# MAIN.net
KiCad netlist of a schematic drawn in Altium Designer
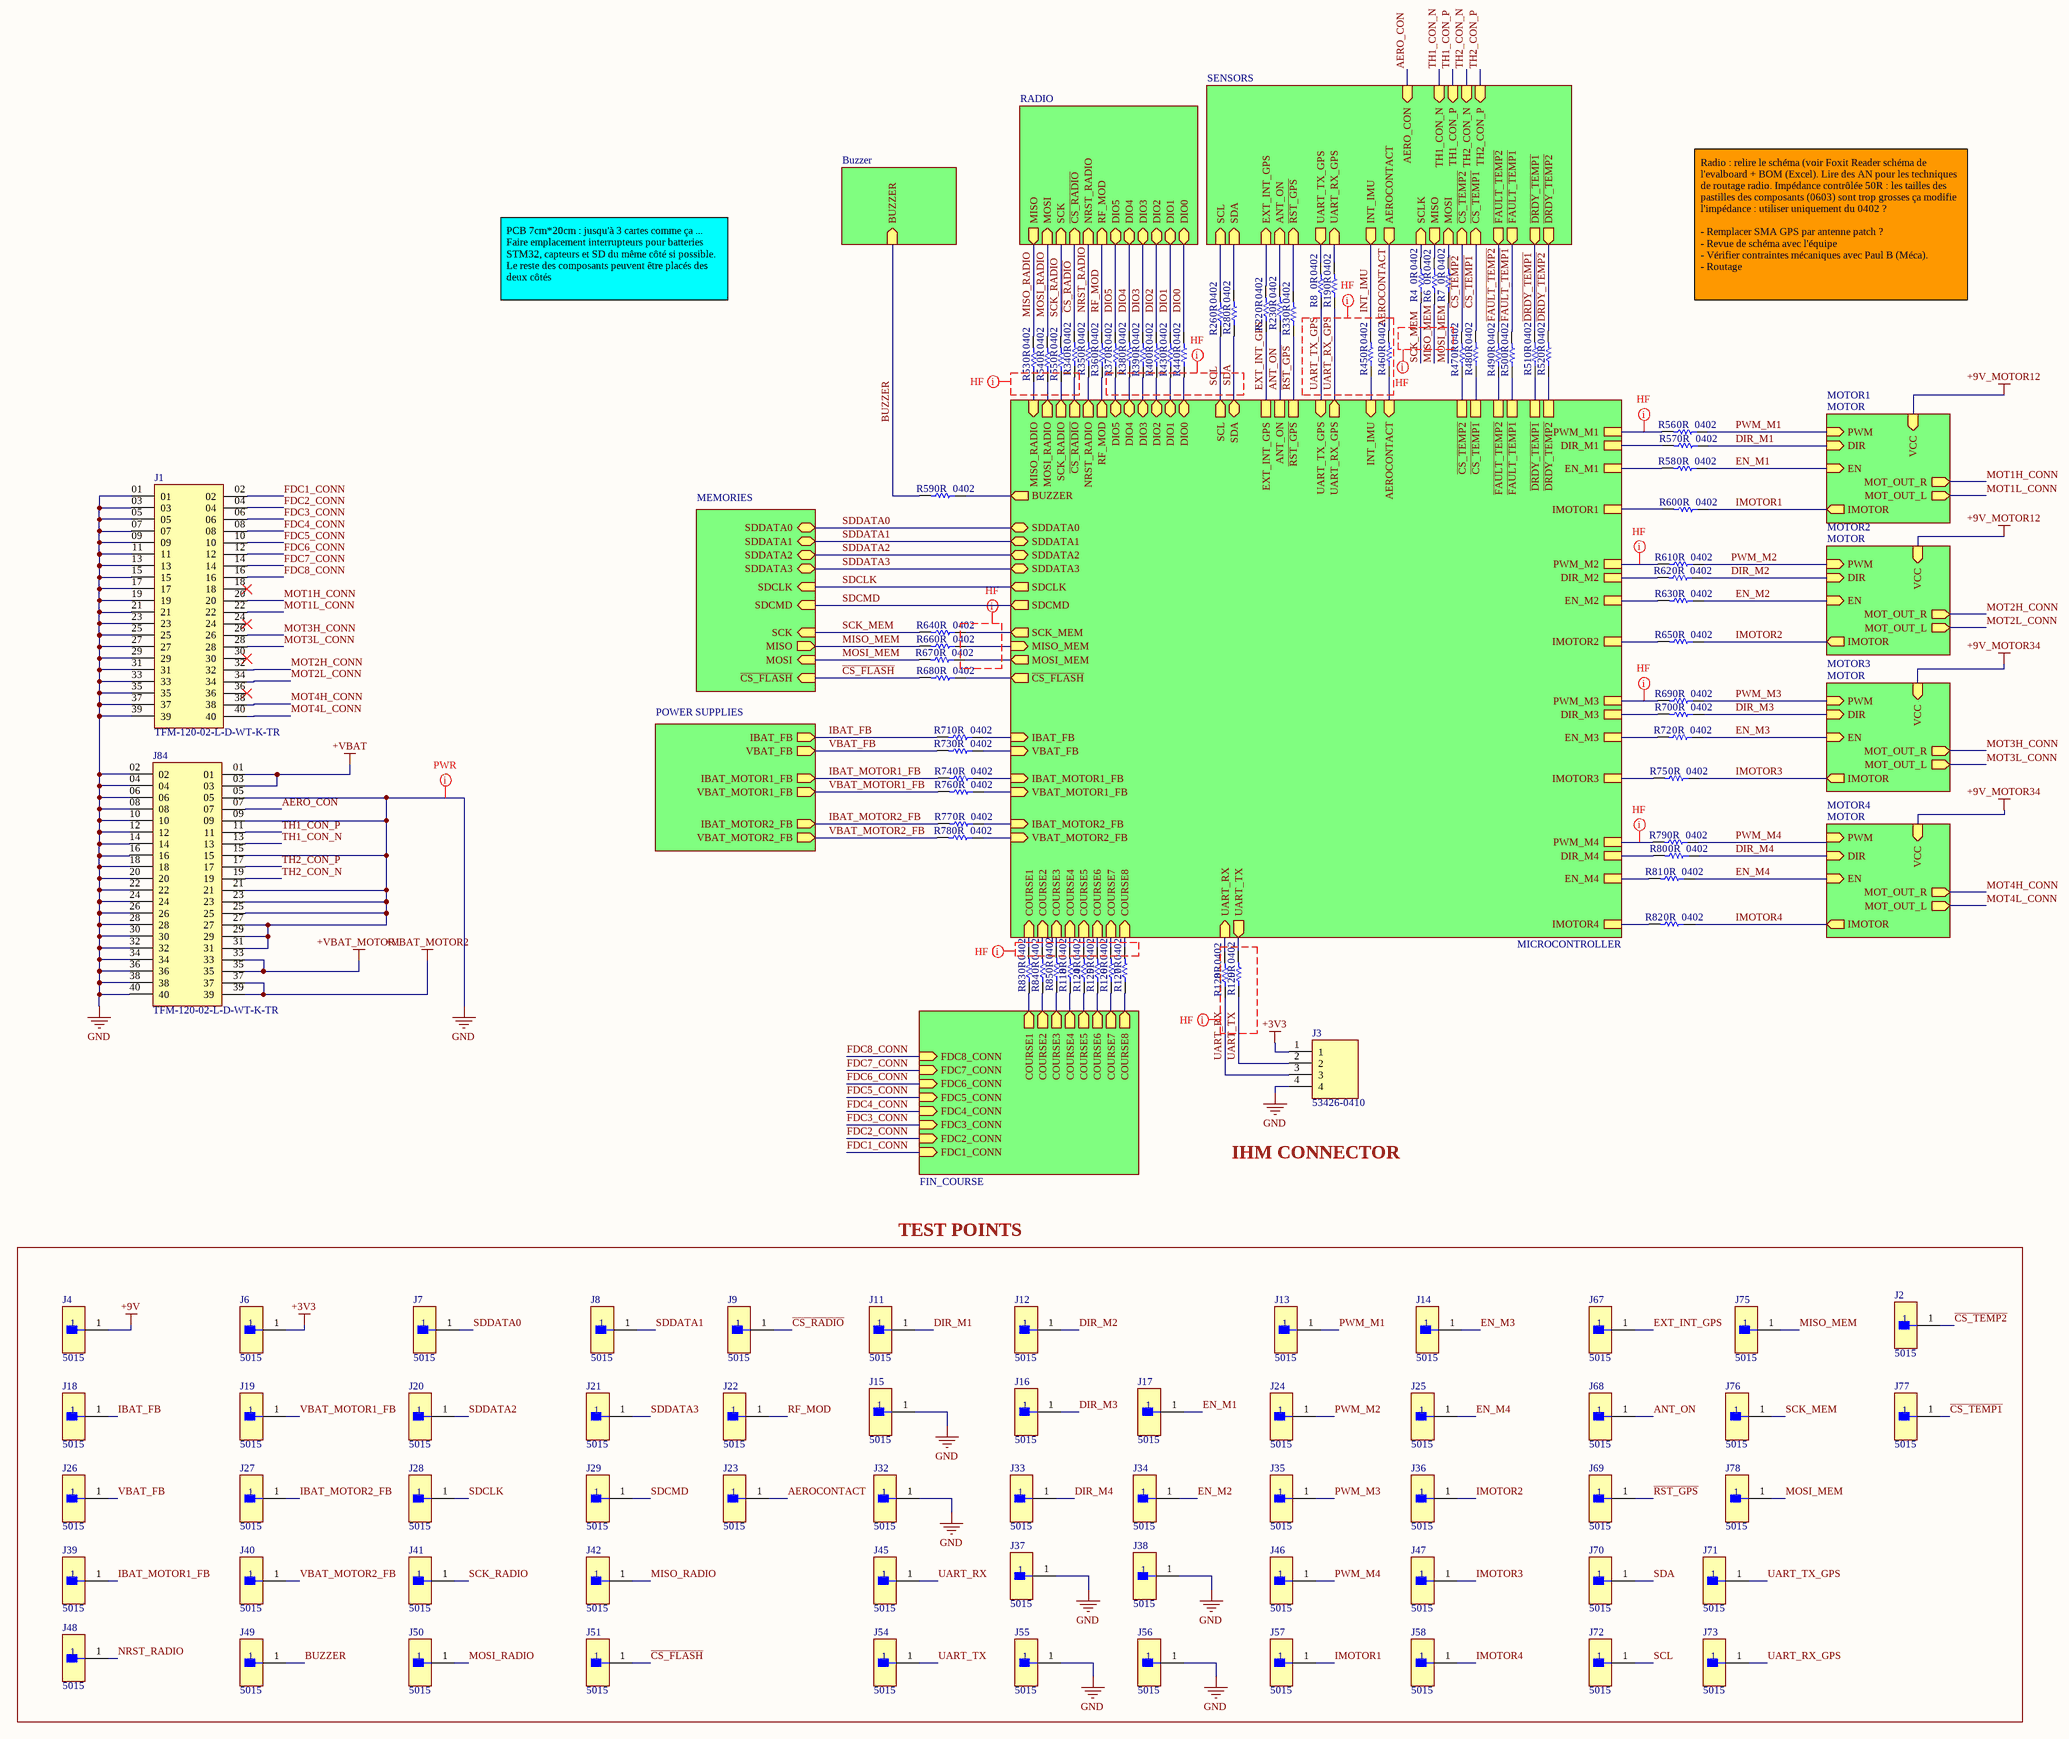
[diagram p0: MAIN.SchDoc]

(export (version "E")
  (design (tool "Eeschema 10.0.6"))
  (components
    (comp (ref "J1")
      (value "TFM-120-02-L-D-WT-K-TR")
      (footprint "TFM-120-02-L-D-WT:SAMTEC_TFM-120-02-L-D-WT-K-TR")
      (fields (field (name "MF") "{'manufacturer': u'Samtec'}"))
      (libsource (lib "*") (part "TFM-120-02-L-D-WT-K-TR"))
    )
    (comp (ref "J2")
      (value "5015")
      (footprint "FP-5015-MFG")
      (description "PC TEST POINT MINIATURE")
      (fields
        (field (name "MANUFACTURER") "keystone")
        (field (name "OCTOPART") "https://octopart.com/5015-keystone-3822")
      )
      (libsource (lib "Altium Content Vault") (part "dd45045ce8184df9e99e12baf3f412c"))
    )
    (comp (ref "J3")
      (value "53426-0410")
      (footprint "SamacSys:SHDRRA4W55P0X250_1X4_1240X1150X690P")
      (description "Connector")
      (fields (field (name "MOUSER PART NUMBER") "538-53426-0410"))
      (libsource (lib "*") (part "53426-0410"))
    )
    (comp (ref "J4")
      (value "5015")
      (footprint "FP-5015-MFG")
      (description "PC TEST POINT MINIATURE")
      (fields
        (field (name "MANUFACTURER") "keystone")
        (field (name "OCTOPART") "https://octopart.com/5015-keystone-3822")
      )
      (libsource (lib "Altium Content Vault") (part "dd45045ce8184df9e99e12baf3f412c"))
    )
    (comp (ref "J6")
      (value "5015")
      (footprint "FP-5015-MFG")
      (description "PC TEST POINT MINIATURE")
      (fields
        (field (name "MANUFACTURER") "keystone")
        (field (name "OCTOPART") "https://octopart.com/5015-keystone-3822")
      )
      (libsource (lib "Altium Content Vault") (part "dd45045ce8184df9e99e12baf3f412c"))
    )
    (comp (ref "J7")
      (value "5015")
      (footprint "FP-5015-MFG")
      (description "PC TEST POINT MINIATURE")
      (fields
        (field (name "MANUFACTURER") "keystone")
        (field (name "OCTOPART") "https://octopart.com/5015-keystone-3822")
      )
      (libsource (lib "Altium Content Vault") (part "dd45045ce8184df9e99e12baf3f412c"))
    )
    (comp (ref "J8")
      (value "5015")
      (footprint "FP-5015-MFG")
      (description "PC TEST POINT MINIATURE")
      (fields
        (field (name "MANUFACTURER") "keystone")
        (field (name "OCTOPART") "https://octopart.com/5015-keystone-3822")
      )
      (libsource (lib "Altium Content Vault") (part "dd45045ce8184df9e99e12baf3f412c"))
    )
    (comp (ref "J9")
      (value "5015")
      (footprint "FP-5015-MFG")
      (description "PC TEST POINT MINIATURE")
      (fields
        (field (name "MANUFACTURER") "keystone")
        (field (name "OCTOPART") "https://octopart.com/5015-keystone-3822")
      )
      (libsource (lib "Altium Content Vault") (part "dd45045ce8184df9e99e12baf3f412c"))
    )
    (comp (ref "J11")
      (value "5015")
      (footprint "FP-5015-MFG")
      (description "PC TEST POINT MINIATURE")
      (fields
        (field (name "MANUFACTURER") "keystone")
        (field (name "OCTOPART") "https://octopart.com/5015-keystone-3822")
      )
      (libsource (lib "Altium Content Vault") (part "dd45045ce8184df9e99e12baf3f412c"))
    )
    (comp (ref "J12")
      (value "5015")
      (footprint "FP-5015-MFG")
      (description "PC TEST POINT MINIATURE")
      (fields
        (field (name "MANUFACTURER") "keystone")
        (field (name "OCTOPART") "https://octopart.com/5015-keystone-3822")
      )
      (libsource (lib "Altium Content Vault") (part "dd45045ce8184df9e99e12baf3f412c"))
    )
    (comp (ref "J13")
      (value "5015")
      (footprint "FP-5015-MFG")
      (description "PC TEST POINT MINIATURE")
      (fields
        (field (name "MANUFACTURER") "keystone")
        (field (name "OCTOPART") "https://octopart.com/5015-keystone-3822")
      )
      (libsource (lib "Altium Content Vault") (part "dd45045ce8184df9e99e12baf3f412c"))
    )
    (comp (ref "J14")
      (value "5015")
      (footprint "FP-5015-MFG")
      (description "PC TEST POINT MINIATURE")
      (fields
        (field (name "MANUFACTURER") "keystone")
        (field (name "OCTOPART") "https://octopart.com/5015-keystone-3822")
      )
      (libsource (lib "Altium Content Vault") (part "dd45045ce8184df9e99e12baf3f412c"))
    )
    (comp (ref "J15")
      (value "5015")
      (footprint "FP-5015-MFG")
      (description "PC TEST POINT MINIATURE")
      (fields
        (field (name "MANUFACTURER") "keystone")
        (field (name "OCTOPART") "https://octopart.com/5015-keystone-3822")
      )
      (libsource (lib "Altium Content Vault") (part "dd45045ce8184df9e99e12baf3f412c"))
    )
    (comp (ref "J16")
      (value "5015")
      (footprint "FP-5015-MFG")
      (description "PC TEST POINT MINIATURE")
      (fields
        (field (name "MANUFACTURER") "keystone")
        (field (name "OCTOPART") "https://octopart.com/5015-keystone-3822")
      )
      (libsource (lib "Altium Content Vault") (part "dd45045ce8184df9e99e12baf3f412c"))
    )
    (comp (ref "J17")
      (value "5015")
      (footprint "FP-5015-MFG")
      (description "PC TEST POINT MINIATURE")
      (fields
        (field (name "MANUFACTURER") "keystone")
        (field (name "OCTOPART") "https://octopart.com/5015-keystone-3822")
      )
      (libsource (lib "Altium Content Vault") (part "dd45045ce8184df9e99e12baf3f412c"))
    )
    (comp (ref "J18")
      (value "5015")
      (footprint "FP-5015-MFG")
      (description "PC TEST POINT MINIATURE")
      (fields
        (field (name "MANUFACTURER") "keystone")
        (field (name "OCTOPART") "https://octopart.com/5015-keystone-3822")
      )
      (libsource (lib "Altium Content Vault") (part "dd45045ce8184df9e99e12baf3f412c"))
    )
    (comp (ref "J19")
      (value "5015")
      (footprint "FP-5015-MFG")
      (description "PC TEST POINT MINIATURE")
      (fields
        (field (name "MANUFACTURER") "keystone")
        (field (name "OCTOPART") "https://octopart.com/5015-keystone-3822")
      )
      (libsource (lib "Altium Content Vault") (part "dd45045ce8184df9e99e12baf3f412c"))
    )
    (comp (ref "J20")
      (value "5015")
      (footprint "FP-5015-MFG")
      (description "PC TEST POINT MINIATURE")
      (fields
        (field (name "MANUFACTURER") "keystone")
        (field (name "OCTOPART") "https://octopart.com/5015-keystone-3822")
      )
      (libsource (lib "Altium Content Vault") (part "dd45045ce8184df9e99e12baf3f412c"))
    )
    (comp (ref "J21")
      (value "5015")
      (footprint "FP-5015-MFG")
      (description "PC TEST POINT MINIATURE")
      (fields
        (field (name "MANUFACTURER") "keystone")
        (field (name "OCTOPART") "https://octopart.com/5015-keystone-3822")
      )
      (libsource (lib "Altium Content Vault") (part "dd45045ce8184df9e99e12baf3f412c"))
    )
    (comp (ref "J22")
      (value "5015")
      (footprint "FP-5015-MFG")
      (description "PC TEST POINT MINIATURE")
      (fields
        (field (name "MANUFACTURER") "keystone")
        (field (name "OCTOPART") "https://octopart.com/5015-keystone-3822")
      )
      (libsource (lib "Altium Content Vault") (part "dd45045ce8184df9e99e12baf3f412c"))
    )
    (comp (ref "J23")
      (value "5015")
      (footprint "FP-5015-MFG")
      (description "PC TEST POINT MINIATURE")
      (fields
        (field (name "MANUFACTURER") "keystone")
        (field (name "OCTOPART") "https://octopart.com/5015-keystone-3822")
      )
      (libsource (lib "Altium Content Vault") (part "dd45045ce8184df9e99e12baf3f412c"))
    )
    (comp (ref "J24")
      (value "5015")
      (footprint "FP-5015-MFG")
      (description "PC TEST POINT MINIATURE")
      (fields
        (field (name "MANUFACTURER") "keystone")
        (field (name "OCTOPART") "https://octopart.com/5015-keystone-3822")
      )
      (libsource (lib "Altium Content Vault") (part "dd45045ce8184df9e99e12baf3f412c"))
    )
    (comp (ref "J25")
      (value "5015")
      (footprint "FP-5015-MFG")
      (description "PC TEST POINT MINIATURE")
      (fields
        (field (name "MANUFACTURER") "keystone")
        (field (name "OCTOPART") "https://octopart.com/5015-keystone-3822")
      )
      (libsource (lib "Altium Content Vault") (part "dd45045ce8184df9e99e12baf3f412c"))
    )
    (comp (ref "J26")
      (value "5015")
      (footprint "FP-5015-MFG")
      (description "PC TEST POINT MINIATURE")
      (fields
        (field (name "MANUFACTURER") "keystone")
        (field (name "OCTOPART") "https://octopart.com/5015-keystone-3822")
      )
      (libsource (lib "Altium Content Vault") (part "dd45045ce8184df9e99e12baf3f412c"))
    )
    (comp (ref "J27")
      (value "5015")
      (footprint "FP-5015-MFG")
      (description "PC TEST POINT MINIATURE")
      (fields
        (field (name "MANUFACTURER") "keystone")
        (field (name "OCTOPART") "https://octopart.com/5015-keystone-3822")
      )
      (libsource (lib "Altium Content Vault") (part "dd45045ce8184df9e99e12baf3f412c"))
    )
    (comp (ref "J28")
      (value "5015")
      (footprint "FP-5015-MFG")
      (description "PC TEST POINT MINIATURE")
      (fields
        (field (name "MANUFACTURER") "keystone")
        (field (name "OCTOPART") "https://octopart.com/5015-keystone-3822")
      )
      (libsource (lib "Altium Content Vault") (part "dd45045ce8184df9e99e12baf3f412c"))
    )
    (comp (ref "J29")
      (value "5015")
      (footprint "FP-5015-MFG")
      (description "PC TEST POINT MINIATURE")
      (fields
        (field (name "MANUFACTURER") "keystone")
        (field (name "OCTOPART") "https://octopart.com/5015-keystone-3822")
      )
      (libsource (lib "Altium Content Vault") (part "dd45045ce8184df9e99e12baf3f412c"))
    )
    (comp (ref "J32")
      (value "5015")
      (footprint "FP-5015-MFG")
      (description "PC TEST POINT MINIATURE")
      (fields
        (field (name "MANUFACTURER") "keystone")
        (field (name "OCTOPART") "https://octopart.com/5015-keystone-3822")
      )
      (libsource (lib "Altium Content Vault") (part "dd45045ce8184df9e99e12baf3f412c"))
    )
    (comp (ref "J33")
      (value "5015")
      (footprint "FP-5015-MFG")
      (description "PC TEST POINT MINIATURE")
      (fields
        (field (name "MANUFACTURER") "keystone")
        (field (name "OCTOPART") "https://octopart.com/5015-keystone-3822")
      )
      (libsource (lib "Altium Content Vault") (part "dd45045ce8184df9e99e12baf3f412c"))
    )
    (comp (ref "J34")
      (value "5015")
      (footprint "FP-5015-MFG")
      (description "PC TEST POINT MINIATURE")
      (fields
        (field (name "MANUFACTURER") "keystone")
        (field (name "OCTOPART") "https://octopart.com/5015-keystone-3822")
      )
      (libsource (lib "Altium Content Vault") (part "dd45045ce8184df9e99e12baf3f412c"))
    )
    (comp (ref "J35")
      (value "5015")
      (footprint "FP-5015-MFG")
      (description "PC TEST POINT MINIATURE")
      (fields
        (field (name "MANUFACTURER") "keystone")
        (field (name "OCTOPART") "https://octopart.com/5015-keystone-3822")
      )
      (libsource (lib "Altium Content Vault") (part "dd45045ce8184df9e99e12baf3f412c"))
    )
    (comp (ref "J36")
      (value "5015")
      (footprint "FP-5015-MFG")
      (description "PC TEST POINT MINIATURE")
      (fields
        (field (name "MANUFACTURER") "keystone")
        (field (name "OCTOPART") "https://octopart.com/5015-keystone-3822")
      )
      (libsource (lib "Altium Content Vault") (part "dd45045ce8184df9e99e12baf3f412c"))
    )
    (comp (ref "J37")
      (value "5015")
      (footprint "FP-5015-MFG")
      (description "PC TEST POINT MINIATURE")
      (fields
        (field (name "MANUFACTURER") "keystone")
        (field (name "OCTOPART") "https://octopart.com/5015-keystone-3822")
      )
      (libsource (lib "Altium Content Vault") (part "dd45045ce8184df9e99e12baf3f412c"))
    )
    (comp (ref "J38")
      (value "5015")
      (footprint "FP-5015-MFG")
      (description "PC TEST POINT MINIATURE")
      (fields
        (field (name "MANUFACTURER") "keystone")
        (field (name "OCTOPART") "https://octopart.com/5015-keystone-3822")
      )
      (libsource (lib "Altium Content Vault") (part "dd45045ce8184df9e99e12baf3f412c"))
    )
    (comp (ref "J39")
      (value "5015")
      (footprint "FP-5015-MFG")
      (description "PC TEST POINT MINIATURE")
      (fields
        (field (name "MANUFACTURER") "keystone")
        (field (name "OCTOPART") "https://octopart.com/5015-keystone-3822")
      )
      (libsource (lib "Altium Content Vault") (part "dd45045ce8184df9e99e12baf3f412c"))
    )
    (comp (ref "J40")
      (value "5015")
      (footprint "FP-5015-MFG")
      (description "PC TEST POINT MINIATURE")
      (fields
        (field (name "MANUFACTURER") "keystone")
        (field (name "OCTOPART") "https://octopart.com/5015-keystone-3822")
      )
      (libsource (lib "Altium Content Vault") (part "dd45045ce8184df9e99e12baf3f412c"))
    )
    (comp (ref "J41")
      (value "5015")
      (footprint "FP-5015-MFG")
      (description "PC TEST POINT MINIATURE")
      (fields
        (field (name "MANUFACTURER") "keystone")
        (field (name "OCTOPART") "https://octopart.com/5015-keystone-3822")
      )
      (libsource (lib "Altium Content Vault") (part "dd45045ce8184df9e99e12baf3f412c"))
    )
    (comp (ref "J42")
      (value "5015")
      (footprint "FP-5015-MFG")
      (description "PC TEST POINT MINIATURE")
      (fields
        (field (name "MANUFACTURER") "keystone")
        (field (name "OCTOPART") "https://octopart.com/5015-keystone-3822")
      )
      (libsource (lib "Altium Content Vault") (part "dd45045ce8184df9e99e12baf3f412c"))
    )
    (comp (ref "J45")
      (value "5015")
      (footprint "FP-5015-MFG")
      (description "PC TEST POINT MINIATURE")
      (fields
        (field (name "MANUFACTURER") "keystone")
        (field (name "OCTOPART") "https://octopart.com/5015-keystone-3822")
      )
      (libsource (lib "Altium Content Vault") (part "dd45045ce8184df9e99e12baf3f412c"))
    )
    (comp (ref "J46")
      (value "5015")
      (footprint "FP-5015-MFG")
      (description "PC TEST POINT MINIATURE")
      (fields
        (field (name "MANUFACTURER") "keystone")
        (field (name "OCTOPART") "https://octopart.com/5015-keystone-3822")
      )
      (libsource (lib "Altium Content Vault") (part "dd45045ce8184df9e99e12baf3f412c"))
    )
    (comp (ref "J47")
      (value "5015")
      (footprint "FP-5015-MFG")
      (description "PC TEST POINT MINIATURE")
      (fields
        (field (name "MANUFACTURER") "keystone")
        (field (name "OCTOPART") "https://octopart.com/5015-keystone-3822")
      )
      (libsource (lib "Altium Content Vault") (part "dd45045ce8184df9e99e12baf3f412c"))
    )
    (comp (ref "J48")
      (value "5015")
      (footprint "FP-5015-MFG")
      (description "PC TEST POINT MINIATURE")
      (fields
        (field (name "MANUFACTURER") "keystone")
        (field (name "OCTOPART") "https://octopart.com/5015-keystone-3822")
      )
      (libsource (lib "Altium Content Vault") (part "dd45045ce8184df9e99e12baf3f412c"))
    )
    (comp (ref "J49")
      (value "5015")
      (footprint "FP-5015-MFG")
      (description "PC TEST POINT MINIATURE")
      (fields
        (field (name "MANUFACTURER") "keystone")
        (field (name "OCTOPART") "https://octopart.com/5015-keystone-3822")
      )
      (libsource (lib "Altium Content Vault") (part "dd45045ce8184df9e99e12baf3f412c"))
    )
    (comp (ref "J50")
      (value "5015")
      (footprint "FP-5015-MFG")
      (description "PC TEST POINT MINIATURE")
      (fields
        (field (name "MANUFACTURER") "keystone")
        (field (name "OCTOPART") "https://octopart.com/5015-keystone-3822")
      )
      (libsource (lib "Altium Content Vault") (part "dd45045ce8184df9e99e12baf3f412c"))
    )
    (comp (ref "J51")
      (value "5015")
      (footprint "FP-5015-MFG")
      (description "PC TEST POINT MINIATURE")
      (fields
        (field (name "MANUFACTURER") "keystone")
        (field (name "OCTOPART") "https://octopart.com/5015-keystone-3822")
      )
      (libsource (lib "Altium Content Vault") (part "dd45045ce8184df9e99e12baf3f412c"))
    )
    (comp (ref "J54")
      (value "5015")
      (footprint "FP-5015-MFG")
      (description "PC TEST POINT MINIATURE")
      (fields
        (field (name "MANUFACTURER") "keystone")
        (field (name "OCTOPART") "https://octopart.com/5015-keystone-3822")
      )
      (libsource (lib "Altium Content Vault") (part "dd45045ce8184df9e99e12baf3f412c"))
    )
    (comp (ref "J55")
      (value "5015")
      (footprint "FP-5015-MFG")
      (description "PC TEST POINT MINIATURE")
      (fields
        (field (name "MANUFACTURER") "keystone")
        (field (name "OCTOPART") "https://octopart.com/5015-keystone-3822")
      )
      (libsource (lib "Altium Content Vault") (part "dd45045ce8184df9e99e12baf3f412c"))
    )
    (comp (ref "J56")
      (value "5015")
      (footprint "FP-5015-MFG")
      (description "PC TEST POINT MINIATURE")
      (fields
        (field (name "MANUFACTURER") "keystone")
        (field (name "OCTOPART") "https://octopart.com/5015-keystone-3822")
      )
      (libsource (lib "Altium Content Vault") (part "dd45045ce8184df9e99e12baf3f412c"))
    )
    (comp (ref "J57")
      (value "5015")
      (footprint "FP-5015-MFG")
      (description "PC TEST POINT MINIATURE")
      (fields
        (field (name "MANUFACTURER") "keystone")
        (field (name "OCTOPART") "https://octopart.com/5015-keystone-3822")
      )
      (libsource (lib "Altium Content Vault") (part "dd45045ce8184df9e99e12baf3f412c"))
    )
    (comp (ref "J58")
      (value "5015")
      (footprint "FP-5015-MFG")
      (description "PC TEST POINT MINIATURE")
      (fields
        (field (name "MANUFACTURER") "keystone")
        (field (name "OCTOPART") "https://octopart.com/5015-keystone-3822")
      )
      (libsource (lib "Altium Content Vault") (part "dd45045ce8184df9e99e12baf3f412c"))
    )
    (comp (ref "J67")
      (value "5015")
      (footprint "FP-5015-MFG")
      (description "PC TEST POINT MINIATURE")
      (fields
        (field (name "MANUFACTURER") "keystone")
        (field (name "OCTOPART") "https://octopart.com/5015-keystone-3822")
      )
      (libsource (lib "Altium Content Vault") (part "dd45045ce8184df9e99e12baf3f412c"))
    )
    (comp (ref "J68")
      (value "5015")
      (footprint "FP-5015-MFG")
      (description "PC TEST POINT MINIATURE")
      (fields
        (field (name "MANUFACTURER") "keystone")
        (field (name "OCTOPART") "https://octopart.com/5015-keystone-3822")
      )
      (libsource (lib "Altium Content Vault") (part "dd45045ce8184df9e99e12baf3f412c"))
    )
    (comp (ref "J69")
      (value "5015")
      (footprint "FP-5015-MFG")
      (description "PC TEST POINT MINIATURE")
      (fields
        (field (name "MANUFACTURER") "keystone")
        (field (name "OCTOPART") "https://octopart.com/5015-keystone-3822")
      )
      (libsource (lib "Altium Content Vault") (part "dd45045ce8184df9e99e12baf3f412c"))
    )
    (comp (ref "J70")
      (value "5015")
      (footprint "FP-5015-MFG")
      (description "PC TEST POINT MINIATURE")
      (fields
        (field (name "MANUFACTURER") "keystone")
        (field (name "OCTOPART") "https://octopart.com/5015-keystone-3822")
      )
      (libsource (lib "Altium Content Vault") (part "dd45045ce8184df9e99e12baf3f412c"))
    )
    (comp (ref "J71")
      (value "5015")
      (footprint "FP-5015-MFG")
      (description "PC TEST POINT MINIATURE")
      (fields
        (field (name "MANUFACTURER") "keystone")
        (field (name "OCTOPART") "https://octopart.com/5015-keystone-3822")
      )
      (libsource (lib "Altium Content Vault") (part "dd45045ce8184df9e99e12baf3f412c"))
    )
    (comp (ref "J72")
      (value "5015")
      (footprint "FP-5015-MFG")
      (description "PC TEST POINT MINIATURE")
      (fields
        (field (name "MANUFACTURER") "keystone")
        (field (name "OCTOPART") "https://octopart.com/5015-keystone-3822")
      )
      (libsource (lib "Altium Content Vault") (part "dd45045ce8184df9e99e12baf3f412c"))
    )
    (comp (ref "J73")
      (value "5015")
      (footprint "FP-5015-MFG")
      (description "PC TEST POINT MINIATURE")
      (fields
        (field (name "MANUFACTURER") "keystone")
        (field (name "OCTOPART") "https://octopart.com/5015-keystone-3822")
      )
      (libsource (lib "Altium Content Vault") (part "dd45045ce8184df9e99e12baf3f412c"))
    )
    (comp (ref "J75")
      (value "5015")
      (footprint "FP-5015-MFG")
      (description "PC TEST POINT MINIATURE")
      (fields
        (field (name "MANUFACTURER") "keystone")
        (field (name "OCTOPART") "https://octopart.com/5015-keystone-3822")
      )
      (libsource (lib "Altium Content Vault") (part "dd45045ce8184df9e99e12baf3f412c"))
    )
    (comp (ref "J76")
      (value "5015")
      (footprint "FP-5015-MFG")
      (description "PC TEST POINT MINIATURE")
      (fields
        (field (name "MANUFACTURER") "keystone")
        (field (name "OCTOPART") "https://octopart.com/5015-keystone-3822")
      )
      (libsource (lib "Altium Content Vault") (part "dd45045ce8184df9e99e12baf3f412c"))
    )
    (comp (ref "J77")
      (value "5015")
      (footprint "FP-5015-MFG")
      (description "PC TEST POINT MINIATURE")
      (fields
        (field (name "MANUFACTURER") "keystone")
        (field (name "OCTOPART") "https://octopart.com/5015-keystone-3822")
      )
      (libsource (lib "Altium Content Vault") (part "dd45045ce8184df9e99e12baf3f412c"))
    )
    (comp (ref "J78")
      (value "5015")
      (footprint "FP-5015-MFG")
      (description "PC TEST POINT MINIATURE")
      (fields
        (field (name "MANUFACTURER") "keystone")
        (field (name "OCTOPART") "https://octopart.com/5015-keystone-3822")
      )
      (libsource (lib "Altium Content Vault") (part "dd45045ce8184df9e99e12baf3f412c"))
    )
    (comp (ref "J84")
      (value "TFM-120-02-L-D-WT-K-TR")
      (footprint "TFM-120-02-L-D-WT:SAMTEC_TFM-120-02-L-D-WT-K-TR")
      (fields (field (name "MF") "{'manufacturer': u'Samtec'}"))
      (libsource (lib "") (part "TFM-120-02-L-D-WT-K-TR_1"))
    )
    (comp (ref "R4")
      (value "CRCW04020000Z0EDHP")
      (footprint "RESC1005X40X25ML05T10")
      (fields
        (field (name "MANUFACTURER") "Vishay Dale")
        (field (name "CASE CODE (IMPERIAL)") "0402")
        (field (name "RESISTANCE") "0R")
      )
      (libsource (lib "Altium Content Vault") (part "RES"))
    )
    (comp (ref "R6")
      (value "CRCW04020000Z0EDHP")
      (footprint "RESC1005X40X25ML05T10")
      (fields
        (field (name "MANUFACTURER") "Vishay Dale")
        (field (name "CASE CODE (IMPERIAL)") "0402")
        (field (name "RESISTANCE") "0R")
      )
      (libsource (lib "Altium Content Vault") (part "RES"))
    )
    (comp (ref "R7")
      (value "CRCW04020000Z0EDHP")
      (footprint "RESC1005X40X25ML05T10")
      (fields
        (field (name "MANUFACTURER") "Vishay Dale")
        (field (name "CASE CODE (IMPERIAL)") "0402")
        (field (name "RESISTANCE") "0R")
      )
      (libsource (lib "Altium Content Vault") (part "RES"))
    )
    (comp (ref "R8")
      (value "CRCW04020000Z0EDHP")
      (footprint "RESC1005X40X25ML05T10")
      (fields
        (field (name "MANUFACTURER") "Vishay Dale")
        (field (name "CASE CODE (IMPERIAL)") "0402")
        (field (name "RESISTANCE") "0R")
      )
      (libsource (lib "Altium Content Vault") (part "RES"))
    )
    (comp (ref "R19")
      (value "CRCW04020000Z0EDHP")
      (footprint "RESC1005X40X25ML05T10")
      (fields
        (field (name "MANUFACTURER") "Vishay Dale")
        (field (name "CASE CODE (IMPERIAL)") "0402")
        (field (name "RESISTANCE") "0R")
      )
      (libsource (lib "Altium Content Vault") (part "RES"))
    )
    (comp (ref "R22")
      (value "CRCW04020000Z0EDHP")
      (footprint "RESC1005X40X25ML05T10")
      (fields
        (field (name "MANUFACTURER") "Vishay Dale")
        (field (name "CASE CODE (IMPERIAL)") "0402")
        (field (name "RESISTANCE") "0R")
      )
      (libsource (lib "Altium Content Vault") (part "RES"))
    )
    (comp (ref "R23")
      (value "CRCW04020000Z0EDHP")
      (footprint "RESC1005X40X25ML05T10")
      (fields
        (field (name "MANUFACTURER") "Vishay Dale")
        (field (name "CASE CODE (IMPERIAL)") "0402")
        (field (name "RESISTANCE") "0R")
      )
      (libsource (lib "Altium Content Vault") (part "RES"))
    )
    (comp (ref "R26")
      (value "CRCW04020000Z0EDHP")
      (footprint "RESC1005X40X25ML05T10")
      (fields
        (field (name "MANUFACTURER") "Vishay Dale")
        (field (name "CASE CODE (IMPERIAL)") "0402")
        (field (name "RESISTANCE") "0R")
      )
      (libsource (lib "Altium Content Vault") (part "RES"))
    )
    (comp (ref "R28")
      (value "CRCW04020000Z0EDHP")
      (footprint "RESC1005X40X25ML05T10")
      (fields
        (field (name "MANUFACTURER") "Vishay Dale")
        (field (name "CASE CODE (IMPERIAL)") "0402")
        (field (name "RESISTANCE") "0R")
      )
      (libsource (lib "Altium Content Vault") (part "RES"))
    )
    (comp (ref "R33")
      (value "CRCW04020000Z0EDHP")
      (footprint "RESC1005X40X25ML05T10")
      (fields
        (field (name "MANUFACTURER") "Vishay Dale")
        (field (name "CASE CODE (IMPERIAL)") "0402")
        (field (name "RESISTANCE") "0R")
      )
      (libsource (lib "Altium Content Vault") (part "RES"))
    )
    (comp (ref "R34")
      (value "CRCW04020000Z0EDHP")
      (footprint "RESC1005X40X25ML05T10")
      (fields
        (field (name "MANUFACTURER") "Vishay Dale")
        (field (name "CASE CODE (IMPERIAL)") "0402")
        (field (name "RESISTANCE") "0R")
      )
      (libsource (lib "Altium Content Vault") (part "RES"))
    )
    (comp (ref "R35")
      (value "CRCW04020000Z0EDHP")
      (footprint "RESC1005X40X25ML05T10")
      (fields
        (field (name "MANUFACTURER") "Vishay Dale")
        (field (name "CASE CODE (IMPERIAL)") "0402")
        (field (name "RESISTANCE") "0R")
      )
      (libsource (lib "Altium Content Vault") (part "RES"))
    )
    (comp (ref "R36")
      (value "CRCW04020000Z0EDHP")
      (footprint "RESC1005X40X25ML05T10")
      (fields
        (field (name "MANUFACTURER") "Vishay Dale")
        (field (name "CASE CODE (IMPERIAL)") "0402")
        (field (name "RESISTANCE") "0R")
      )
      (libsource (lib "Altium Content Vault") (part "RES"))
    )
    (comp (ref "R37")
      (value "CRCW04020000Z0EDHP")
      (footprint "RESC1005X40X25ML05T10")
      (fields
        (field (name "MANUFACTURER") "Vishay Dale")
        (field (name "CASE CODE (IMPERIAL)") "0402")
        (field (name "RESISTANCE") "0R")
      )
      (libsource (lib "Altium Content Vault") (part "RES"))
    )
    (comp (ref "R38")
      (value "CRCW04020000Z0EDHP")
      (footprint "RESC1005X40X25ML05T10")
      (fields
        (field (name "MANUFACTURER") "Vishay Dale")
        (field (name "CASE CODE (IMPERIAL)") "0402")
        (field (name "RESISTANCE") "0R")
      )
      (libsource (lib "Altium Content Vault") (part "RES"))
    )
    (comp (ref "R39")
      (value "CRCW04020000Z0EDHP")
      (footprint "RESC1005X40X25ML05T10")
      (fields
        (field (name "MANUFACTURER") "Vishay Dale")
        (field (name "CASE CODE (IMPERIAL)") "0402")
        (field (name "RESISTANCE") "0R")
      )
      (libsource (lib "Altium Content Vault") (part "RES"))
    )
    (comp (ref "R40")
      (value "CRCW04020000Z0EDHP")
      (footprint "RESC1005X40X25ML05T10")
      (fields
        (field (name "MANUFACTURER") "Vishay Dale")
        (field (name "CASE CODE (IMPERIAL)") "0402")
        (field (name "RESISTANCE") "0R")
      )
      (libsource (lib "Altium Content Vault") (part "RES"))
    )
    (comp (ref "R43")
      (value "CRCW04020000Z0EDHP")
      (footprint "RESC1005X40X25ML05T10")
      (fields
        (field (name "MANUFACTURER") "Vishay Dale")
        (field (name "CASE CODE (IMPERIAL)") "0402")
        (field (name "RESISTANCE") "0R")
      )
      (libsource (lib "Altium Content Vault") (part "RES"))
    )
    (comp (ref "R44")
      (value "CRCW04020000Z0EDHP")
      (footprint "RESC1005X40X25ML05T10")
      (fields
        (field (name "MANUFACTURER") "Vishay Dale")
        (field (name "CASE CODE (IMPERIAL)") "0402")
        (field (name "RESISTANCE") "0R")
      )
      (libsource (lib "Altium Content Vault") (part "RES"))
    )
    (comp (ref "R45")
      (value "CRCW04020000Z0EDHP")
      (footprint "RESC1005X40X25ML05T10")
      (fields
        (field (name "MANUFACTURER") "Vishay Dale")
        (field (name "CASE CODE (IMPERIAL)") "0402")
        (field (name "RESISTANCE") "0R")
      )
      (libsource (lib "Altium Content Vault") (part "RES"))
    )
    (comp (ref "R46")
      (value "CRCW04020000Z0EDHP")
      (footprint "RESC1005X40X25ML05T10")
      (fields
        (field (name "MANUFACTURER") "Vishay Dale")
        (field (name "CASE CODE (IMPERIAL)") "0402")
        (field (name "RESISTANCE") "0R")
      )
      (libsource (lib "Altium Content Vault") (part "RES"))
    )
    (comp (ref "R47")
      (value "CRCW04020000Z0EDHP")
      (footprint "RESC1005X40X25ML05T10")
      (fields
        (field (name "MANUFACTURER") "Vishay Dale")
        (field (name "CASE CODE (IMPERIAL)") "0402")
        (field (name "RESISTANCE") "0R")
      )
      (libsource (lib "Altium Content Vault") (part "RES"))
    )
    (comp (ref "R48")
      (value "CRCW04020000Z0EDHP")
      (footprint "RESC1005X40X25ML05T10")
      (fields
        (field (name "MANUFACTURER") "Vishay Dale")
        (field (name "CASE CODE (IMPERIAL)") "0402")
        (field (name "RESISTANCE") "0R")
      )
      (libsource (lib "Altium Content Vault") (part "RES"))
    )
    (comp (ref "R49")
      (value "CRCW04020000Z0EDHP")
      (footprint "RESC1005X40X25ML05T10")
      (fields
        (field (name "MANUFACTURER") "Vishay Dale")
        (field (name "CASE CODE (IMPERIAL)") "0402")
        (field (name "RESISTANCE") "0R")
      )
      (libsource (lib "Altium Content Vault") (part "RES"))
    )
    (comp (ref "R50")
      (value "CRCW04020000Z0EDHP")
      (footprint "RESC1005X40X25ML05T10")
      (fields
        (field (name "MANUFACTURER") "Vishay Dale")
        (field (name "CASE CODE (IMPERIAL)") "0402")
        (field (name "RESISTANCE") "0R")
      )
      (libsource (lib "Altium Content Vault") (part "RES"))
    )
    (comp (ref "R51")
      (value "CRCW04020000Z0EDHP")
      (footprint "RESC1005X40X25ML05T10")
      (fields
        (field (name "MANUFACTURER") "Vishay Dale")
        (field (name "CASE CODE (IMPERIAL)") "0402")
        (field (name "RESISTANCE") "0R")
      )
      (libsource (lib "Altium Content Vault") (part "RES"))
    )
    (comp (ref "R52")
      (value "CRCW04020000Z0EDHP")
      (footprint "RESC1005X40X25ML05T10")
      (fields
        (field (name "MANUFACTURER") "Vishay Dale")
        (field (name "CASE CODE (IMPERIAL)") "0402")
        (field (name "RESISTANCE") "0R")
      )
      (libsource (lib "Altium Content Vault") (part "RES"))
    )
    (comp (ref "R53")
      (value "CRCW04020000Z0EDHP")
      (footprint "RESC1005X40X25ML05T10")
      (fields
        (field (name "MANUFACTURER") "Vishay Dale")
        (field (name "CASE CODE (IMPERIAL)") "0402")
        (field (name "RESISTANCE") "0R")
      )
      (libsource (lib "Altium Content Vault") (part "RES"))
    )
    (comp (ref "R54")
      (value "CRCW04020000Z0EDHP")
      (footprint "RESC1005X40X25ML05T10")
      (fields
        (field (name "MANUFACTURER") "Vishay Dale")
        (field (name "CASE CODE (IMPERIAL)") "0402")
        (field (name "RESISTANCE") "0R")
      )
      (libsource (lib "Altium Content Vault") (part "RES"))
    )
    (comp (ref "R55")
      (value "CRCW04020000Z0EDHP")
      (footprint "RESC1005X40X25ML05T10")
      (fields
        (field (name "MANUFACTURER") "Vishay Dale")
        (field (name "CASE CODE (IMPERIAL)") "0402")
        (field (name "RESISTANCE") "0R")
      )
      (libsource (lib "Altium Content Vault") (part "RES"))
    )
    (comp (ref "R56")
      (value "CRCW04020000Z0EDHP")
      (footprint "RESC1005X40X25ML05T10")
      (fields
        (field (name "MANUFACTURER") "Vishay Dale")
        (field (name "CASE CODE (IMPERIAL)") "0402")
        (field (name "RESISTANCE") "0R")
      )
      (libsource (lib "Altium Content Vault") (part "RES"))
    )
    (comp (ref "R57")
      (value "CRCW04020000Z0EDHP")
      (footprint "RESC1005X40X25ML05T10")
      (fields
        (field (name "MANUFACTURER") "Vishay Dale")
        (field (name "CASE CODE (IMPERIAL)") "0402")
        (field (name "RESISTANCE") "0R")
      )
      (libsource (lib "Altium Content Vault") (part "RES"))
    )
    (comp (ref "R58")
      (value "CRCW04020000Z0EDHP")
      (footprint "RESC1005X40X25ML05T10")
      (fields
        (field (name "MANUFACTURER") "Vishay Dale")
        (field (name "CASE CODE (IMPERIAL)") "0402")
        (field (name "RESISTANCE") "0R")
      )
      (libsource (lib "Altium Content Vault") (part "RES"))
    )
    (comp (ref "R59")
      (value "CRCW04020000Z0EDHP")
      (footprint "RESC1005X40X25ML05T10")
      (fields
        (field (name "MANUFACTURER") "Vishay Dale")
        (field (name "CASE CODE (IMPERIAL)") "0402")
        (field (name "RESISTANCE") "0R")
      )
      (libsource (lib "Altium Content Vault") (part "RES"))
    )
    (comp (ref "R60")
      (value "CRCW04020000Z0EDHP")
      (footprint "RESC1005X40X25ML05T10")
      (fields
        (field (name "MANUFACTURER") "Vishay Dale")
        (field (name "CASE CODE (IMPERIAL)") "0402")
        (field (name "RESISTANCE") "0R")
      )
      (libsource (lib "Altium Content Vault") (part "RES"))
    )
    (comp (ref "R61")
      (value "CRCW04020000Z0EDHP")
      (footprint "RESC1005X40X25ML05T10")
      (fields
        (field (name "MANUFACTURER") "Vishay Dale")
        (field (name "CASE CODE (IMPERIAL)") "0402")
        (field (name "RESISTANCE") "0R")
      )
      (libsource (lib "Altium Content Vault") (part "RES"))
    )
    (comp (ref "R62")
      (value "CRCW04020000Z0EDHP")
      (footprint "RESC1005X40X25ML05T10")
      (fields
        (field (name "MANUFACTURER") "Vishay Dale")
        (field (name "CASE CODE (IMPERIAL)") "0402")
        (field (name "RESISTANCE") "0R")
      )
      (libsource (lib "Altium Content Vault") (part "RES"))
    )
    (comp (ref "R63")
      (value "CRCW04020000Z0EDHP")
      (footprint "RESC1005X40X25ML05T10")
      (fields
        (field (name "MANUFACTURER") "Vishay Dale")
        (field (name "CASE CODE (IMPERIAL)") "0402")
        (field (name "RESISTANCE") "0R")
      )
      (libsource (lib "Altium Content Vault") (part "RES"))
    )
    (comp (ref "R64")
      (value "CRCW04020000Z0EDHP")
      (footprint "RESC1005X40X25ML05T10")
      (fields
        (field (name "MANUFACTURER") "Vishay Dale")
        (field (name "CASE CODE (IMPERIAL)") "0402")
        (field (name "RESISTANCE") "0R")
      )
      (libsource (lib "Altium Content Vault") (part "RES"))
    )
    (comp (ref "R65")
      (value "CRCW04020000Z0EDHP")
      (footprint "RESC1005X40X25ML05T10")
      (fields
        (field (name "MANUFACTURER") "Vishay Dale")
        (field (name "CASE CODE (IMPERIAL)") "0402")
        (field (name "RESISTANCE") "0R")
      )
      (libsource (lib "Altium Content Vault") (part "RES"))
    )
    (comp (ref "R66")
      (value "CRCW04020000Z0EDHP")
      (footprint "RESC1005X40X25ML05T10")
      (fields
        (field (name "MANUFACTURER") "Vishay Dale")
        (field (name "CASE CODE (IMPERIAL)") "0402")
        (field (name "RESISTANCE") "0R")
      )
      (libsource (lib "Altium Content Vault") (part "RES"))
    )
    (comp (ref "R67")
      (value "CRCW04020000Z0EDHP")
      (footprint "RESC1005X40X25ML05T10")
      (fields
        (field (name "MANUFACTURER") "Vishay Dale")
        (field (name "CASE CODE (IMPERIAL)") "0402")
        (field (name "RESISTANCE") "0R")
      )
      (libsource (lib "Altium Content Vault") (part "RES"))
    )
    (comp (ref "R68")
      (value "CRCW04020000Z0EDHP")
      (footprint "RESC1005X40X25ML05T10")
      (fields
        (field (name "MANUFACTURER") "Vishay Dale")
        (field (name "CASE CODE (IMPERIAL)") "0402")
        (field (name "RESISTANCE") "0R")
      )
      (libsource (lib "Altium Content Vault") (part "RES"))
    )
    (comp (ref "R69")
      (value "CRCW04020000Z0EDHP")
      (footprint "RESC1005X40X25ML05T10")
      (fields
        (field (name "MANUFACTURER") "Vishay Dale")
        (field (name "CASE CODE (IMPERIAL)") "0402")
        (field (name "RESISTANCE") "0R")
      )
      (libsource (lib "Altium Content Vault") (part "RES"))
    )
    (comp (ref "R70")
      (value "CRCW04020000Z0EDHP")
      (footprint "RESC1005X40X25ML05T10")
      (fields
        (field (name "MANUFACTURER") "Vishay Dale")
        (field (name "CASE CODE (IMPERIAL)") "0402")
        (field (name "RESISTANCE") "0R")
      )
      (libsource (lib "Altium Content Vault") (part "RES"))
    )
    (comp (ref "R71")
      (value "CRCW04020000Z0EDHP")
      (footprint "RESC1005X40X25ML05T10")
      (fields
        (field (name "MANUFACTURER") "Vishay Dale")
        (field (name "CASE CODE (IMPERIAL)") "0402")
        (field (name "RESISTANCE") "0R")
      )
      (libsource (lib "Altium Content Vault") (part "RES"))
    )
    (comp (ref "R72")
      (value "CRCW04020000Z0EDHP")
      (footprint "RESC1005X40X25ML05T10")
      (fields
        (field (name "MANUFACTURER") "Vishay Dale")
        (field (name "CASE CODE (IMPERIAL)") "0402")
        (field (name "RESISTANCE") "0R")
      )
      (libsource (lib "Altium Content Vault") (part "RES"))
    )
    (comp (ref "R73")
      (value "CRCW04020000Z0EDHP")
      (footprint "RESC1005X40X25ML05T10")
      (fields
        (field (name "MANUFACTURER") "Vishay Dale")
        (field (name "CASE CODE (IMPERIAL)") "0402")
        (field (name "RESISTANCE") "0R")
      )
      (libsource (lib "Altium Content Vault") (part "RES"))
    )
    (comp (ref "R74")
      (value "CRCW04020000Z0EDHP")
      (footprint "RESC1005X40X25ML05T10")
      (fields
        (field (name "MANUFACTURER") "Vishay Dale")
        (field (name "CASE CODE (IMPERIAL)") "0402")
        (field (name "RESISTANCE") "0R")
      )
      (libsource (lib "Altium Content Vault") (part "RES"))
    )
    (comp (ref "R75")
      (value "CRCW04020000Z0EDHP")
      (footprint "RESC1005X40X25ML05T10")
      (fields
        (field (name "MANUFACTURER") "Vishay Dale")
        (field (name "CASE CODE (IMPERIAL)") "0402")
        (field (name "RESISTANCE") "0R")
      )
      (libsource (lib "Altium Content Vault") (part "RES"))
    )
    (comp (ref "R76")
      (value "CRCW04020000Z0EDHP")
      (footprint "RESC1005X40X25ML05T10")
      (fields
        (field (name "MANUFACTURER") "Vishay Dale")
        (field (name "CASE CODE (IMPERIAL)") "0402")
        (field (name "RESISTANCE") "0R")
      )
      (libsource (lib "Altium Content Vault") (part "RES"))
    )
    (comp (ref "R77")
      (value "CRCW04020000Z0EDHP")
      (footprint "RESC1005X40X25ML05T10")
      (fields
        (field (name "MANUFACTURER") "Vishay Dale")
        (field (name "CASE CODE (IMPERIAL)") "0402")
        (field (name "RESISTANCE") "0R")
      )
      (libsource (lib "Altium Content Vault") (part "RES"))
    )
    (comp (ref "R78")
      (value "CRCW04020000Z0EDHP")
      (footprint "RESC1005X40X25ML05T10")
      (fields
        (field (name "MANUFACTURER") "Vishay Dale")
        (field (name "CASE CODE (IMPERIAL)") "0402")
        (field (name "RESISTANCE") "0R")
      )
      (libsource (lib "Altium Content Vault") (part "RES"))
    )
    (comp (ref "R79")
      (value "CRCW04020000Z0EDHP")
      (footprint "RESC1005X40X25ML05T10")
      (fields
        (field (name "MANUFACTURER") "Vishay Dale")
        (field (name "CASE CODE (IMPERIAL)") "0402")
        (field (name "RESISTANCE") "0R")
      )
      (libsource (lib "Altium Content Vault") (part "RES"))
    )
    (comp (ref "R80")
      (value "CRCW04020000Z0EDHP")
      (footprint "RESC1005X40X25ML05T10")
      (fields
        (field (name "MANUFACTURER") "Vishay Dale")
        (field (name "CASE CODE (IMPERIAL)") "0402")
        (field (name "RESISTANCE") "0R")
      )
      (libsource (lib "Altium Content Vault") (part "RES"))
    )
    (comp (ref "R81")
      (value "CRCW04020000Z0EDHP")
      (footprint "RESC1005X40X25ML05T10")
      (fields
        (field (name "MANUFACTURER") "Vishay Dale")
        (field (name "CASE CODE (IMPERIAL)") "0402")
        (field (name "RESISTANCE") "0R")
      )
      (libsource (lib "Altium Content Vault") (part "RES"))
    )
    (comp (ref "R82")
      (value "CRCW04020000Z0EDHP")
      (footprint "RESC1005X40X25ML05T10")
      (fields
        (field (name "MANUFACTURER") "Vishay Dale")
        (field (name "CASE CODE (IMPERIAL)") "0402")
        (field (name "RESISTANCE") "0R")
      )
      (libsource (lib "Altium Content Vault") (part "RES"))
    )
    (comp (ref "R83")
      (value "CRCW04020000Z0EDHP")
      (footprint "RESC1005X40X25ML05T10")
      (fields
        (field (name "MANUFACTURER") "Vishay Dale")
        (field (name "CASE CODE (IMPERIAL)") "0402")
        (field (name "RESISTANCE") "0R")
      )
      (libsource (lib "Altium Content Vault") (part "RES"))
    )
    (comp (ref "R84")
      (value "CRCW04020000Z0EDHP")
      (footprint "RESC1005X40X25ML05T10")
      (fields
        (field (name "MANUFACTURER") "Vishay Dale")
        (field (name "CASE CODE (IMPERIAL)") "0402")
        (field (name "RESISTANCE") "0R")
      )
      (libsource (lib "Altium Content Vault") (part "RES"))
    )
    (comp (ref "R85")
      (value "CRCW04020000Z0EDHP")
      (footprint "RESC1005X40X25ML05T10")
      (fields
        (field (name "MANUFACTURER") "Vishay Dale")
        (field (name "CASE CODE (IMPERIAL)") "0402")
        (field (name "RESISTANCE") "0R")
      )
      (libsource (lib "Altium Content Vault") (part "RES"))
    )
    (comp (ref "R118")
      (value "CRCW04020000Z0EDHP")
      (footprint "RESC1005X40X25ML05T10")
      (fields
        (field (name "MANUFACTURER") "Vishay Dale")
        (field (name "CASE CODE (IMPERIAL)") "0402")
        (field (name "RESISTANCE") "0R")
      )
      (libsource (lib "Altium Content Vault") (part "RES"))
    )
    (comp (ref "R124")
      (value "CRCW04020000Z0EDHP")
      (footprint "RESC1005X40X25ML05T10")
      (fields
        (field (name "MANUFACTURER") "Vishay Dale")
        (field (name "CASE CODE (IMPERIAL)") "0402")
        (field (name "RESISTANCE") "0R")
      )
      (libsource (lib "Altium Content Vault") (part "RES"))
    )
    (comp (ref "R125")
      (value "CRCW04020000Z0EDHP")
      (footprint "RESC1005X40X25ML05T10")
      (fields
        (field (name "MANUFACTURER") "Vishay Dale")
        (field (name "CASE CODE (IMPERIAL)") "0402")
        (field (name "RESISTANCE") "0R")
      )
      (libsource (lib "Altium Content Vault") (part "RES"))
    )
    (comp (ref "R126")
      (value "CRCW04020000Z0EDHP")
      (footprint "RESC1005X40X25ML05T10")
      (fields
        (field (name "MANUFACTURER") "Vishay Dale")
        (field (name "CASE CODE (IMPERIAL)") "0402")
        (field (name "RESISTANCE") "0R")
      )
      (libsource (lib "Altium Content Vault") (part "RES"))
    )
    (comp (ref "R127")
      (value "CRCW04020000Z0EDHP")
      (footprint "RESC1005X40X25ML05T10")
      (fields
        (field (name "MANUFACTURER") "Vishay Dale")
        (field (name "CASE CODE (IMPERIAL)") "0402")
        (field (name "RESISTANCE") "0R")
      )
      (libsource (lib "Altium Content Vault") (part "RES"))
    )
    (comp (ref "R128")
      (value "CRCW04020000Z0EDHP")
      (footprint "RESC1005X40X25ML05T10")
      (fields
        (field (name "MANUFACTURER") "Vishay Dale")
        (field (name "CASE CODE (IMPERIAL)") "0402")
        (field (name "RESISTANCE") "0R")
      )
      (libsource (lib "Altium Content Vault") (part "RES"))
    )
    (comp (ref "R129")
      (value "CRCW04020000Z0EDHP")
      (footprint "RESC1005X40X25ML05T10")
      (fields
        (field (name "MANUFACTURER") "Vishay Dale")
        (field (name "CASE CODE (IMPERIAL)") "0402")
        (field (name "RESISTANCE") "0R")
      )
      (libsource (lib "Altium Content Vault") (part "RES"))
    )
  )
  (nets
    (net (code "1") (name "+3V3") (class "Default")
      (node (ref "J3") (pin "1") (pinfunction "1_1") (pintype "passive"))
      (node (ref "J6") (pin "1") (pinfunction "1_1") (pintype "passive"))
    )
    (net (code "2") (name "+9V") (class "Default")
      (node (ref "J4") (pin "1") (pinfunction "1_1") (pintype "passive"))
    )
    (net (code "5") (name "+VBAT") (class "Default")
      (node (ref "J84") (pin "01") (pinfunction "01_01") (pintype "passive"))
      (node (ref "J84") (pin "03") (pinfunction "03_03") (pintype "passive"))
    )
    (net (code "6") (name "+VBAT_MOTOR1") (class "Default")
      (node (ref "J84") (pin "33") (pinfunction "33_33") (pintype "passive"))
      (node (ref "J84") (pin "35") (pinfunction "35_35") (pintype "passive"))
    )
    (net (code "7") (name "+VBAT_MOTOR2") (class "Default")
      (node (ref "J84") (pin "37") (pinfunction "37_37") (pintype "passive"))
      (node (ref "J84") (pin "39") (pinfunction "39_39") (pintype "passive"))
    )
    (net (code "8") (name "/AEROCONTACT") (class "Default")
      (node (ref "J23") (pin "1") (pinfunction "1_1") (pintype "passive"))
      (node (ref "R46") (pin "2") (pinfunction "2_2") (pintype "passive"))
    )
    (net (code "9") (name "/AEROCONTACT_1") (class "Default")
      (node (ref "R46") (pin "1") (pinfunction "1_1") (pintype "passive"))
    )
    (net (code "10") (name "/AERO_CON") (class "Default")
      (node (ref "J84") (pin "07") (pinfunction "07_07") (pintype "passive"))
    )
    (net (code "11") (name "/ANT_ON") (class "Default")
      (node (ref "J68") (pin "1") (pinfunction "1_1") (pintype "passive"))
      (node (ref "R23") (pin "1") (pinfunction "1_1") (pintype "passive"))
    )
    (net (code "12") (name "/ANT_ON_1") (class "Default")
      (node (ref "R23") (pin "2") (pinfunction "2_2") (pintype "passive"))
    )
    (net (code "13") (name "/BUZZER") (class "Default")
      (node (ref "J49") (pin "1") (pinfunction "1_1") (pintype "passive"))
      (node (ref "R59") (pin "2") (pinfunction "2_2") (pintype "passive"))
    )
    (net (code "14") (name "/BUZZER_1") (class "Default")
      (node (ref "R59") (pin "1") (pinfunction "1_1") (pintype "passive"))
    )
    (net (code "15") (name "/COURSE1") (class "Default")
      (node (ref "R83") (pin "2") (pinfunction "2_2") (pintype "passive"))
    )
    (net (code "16") (name "/COURSE1_1") (class "Default")
      (node (ref "R83") (pin "1") (pinfunction "1_1") (pintype "passive"))
    )
    (net (code "17") (name "/COURSE2") (class "Default")
      (node (ref "R84") (pin "2") (pinfunction "2_2") (pintype "passive"))
    )
    (net (code "18") (name "/COURSE2_1") (class "Default")
      (node (ref "R84") (pin "1") (pinfunction "1_1") (pintype "passive"))
    )
    (net (code "19") (name "/COURSE3") (class "Default")
      (node (ref "R85") (pin "2") (pinfunction "2_2") (pintype "passive"))
    )
    (net (code "20") (name "/COURSE3_1") (class "Default")
      (node (ref "R85") (pin "1") (pinfunction "1_1") (pintype "passive"))
    )
    (net (code "21") (name "/COURSE4") (class "Default")
      (node (ref "R118") (pin "2") (pinfunction "2_2") (pintype "passive"))
    )
    (net (code "22") (name "/COURSE4_1") (class "Default")
      (node (ref "R118") (pin "1") (pinfunction "1_1") (pintype "passive"))
    )
    (net (code "23") (name "/COURSE5") (class "Default")
      (node (ref "R124") (pin "2") (pinfunction "2_2") (pintype "passive"))
    )
    (net (code "24") (name "/COURSE5_1") (class "Default")
      (node (ref "R124") (pin "1") (pinfunction "1_1") (pintype "passive"))
    )
    (net (code "25") (name "/COURSE6") (class "Default")
      (node (ref "R125") (pin "2") (pinfunction "2_2") (pintype "passive"))
    )
    (net (code "26") (name "/COURSE6_1") (class "Default")
      (node (ref "R125") (pin "1") (pinfunction "1_1") (pintype "passive"))
    )
    (net (code "27") (name "/COURSE7") (class "Default")
      (node (ref "R126") (pin "2") (pinfunction "2_2") (pintype "passive"))
    )
    (net (code "28") (name "/COURSE7_1") (class "Default")
      (node (ref "R126") (pin "1") (pinfunction "1_1") (pintype "passive"))
    )
    (net (code "29") (name "/COURSE8") (class "Default")
      (node (ref "R127") (pin "2") (pinfunction "2_2") (pintype "passive"))
    )
    (net (code "30") (name "/COURSE8_1") (class "Default")
      (node (ref "R127") (pin "1") (pinfunction "1_1") (pintype "passive"))
    )
    (net (code "31") (name "/CS_FLASH") (class "Default")
      (node (ref "J51") (pin "1") (pinfunction "1_1") (pintype "passive"))
      (node (ref "R68") (pin "2") (pinfunction "2_2") (pintype "passive"))
    )
    (net (code "32") (name "/CS_FLASH_1") (class "Default")
      (node (ref "R68") (pin "1") (pinfunction "1_1") (pintype "passive"))
    )
    (net (code "33") (name "/CS_RADIO") (class "Default")
      (node (ref "J9") (pin "1") (pinfunction "1_1") (pintype "passive"))
      (node (ref "R34") (pin "2") (pinfunction "2_2") (pintype "passive"))
    )
    (net (code "34") (name "/CS_RADIO_1") (class "Default")
      (node (ref "R34") (pin "1") (pinfunction "1_1") (pintype "passive"))
    )
    (net (code "35") (name "/CS_TEMP1") (class "Default")
      (node (ref "J77") (pin "1") (pinfunction "1_1") (pintype "passive"))
      (node (ref "R48") (pin "2") (pinfunction "2_2") (pintype "passive"))
    )
    (net (code "36") (name "/CS_TEMP1_1") (class "Default")
      (node (ref "R48") (pin "1") (pinfunction "1_1") (pintype "passive"))
    )
    (net (code "37") (name "/CS_TEMP2") (class "Default")
      (node (ref "J2") (pin "1") (pinfunction "1_1") (pintype "passive"))
      (node (ref "R47") (pin "2") (pinfunction "2_2") (pintype "passive"))
    )
    (net (code "38") (name "/CS_TEMP2_1") (class "Default")
      (node (ref "R47") (pin "1") (pinfunction "1_1") (pintype "passive"))
    )
    (net (code "39") (name "/DIO0") (class "Default")
      (node (ref "R44") (pin "2") (pinfunction "2_2") (pintype "passive"))
    )
    (net (code "40") (name "/DIO0_1") (class "Default")
      (node (ref "R44") (pin "1") (pinfunction "1_1") (pintype "passive"))
    )
    (net (code "41") (name "/DIO1") (class "Default")
      (node (ref "R43") (pin "2") (pinfunction "2_2") (pintype "passive"))
    )
    (net (code "42") (name "/DIO1_1") (class "Default")
      (node (ref "R43") (pin "1") (pinfunction "1_1") (pintype "passive"))
    )
    (net (code "43") (name "/DIO2") (class "Default")
      (node (ref "R40") (pin "2") (pinfunction "2_2") (pintype "passive"))
    )
    (net (code "44") (name "/DIO2_1") (class "Default")
      (node (ref "R40") (pin "1") (pinfunction "1_1") (pintype "passive"))
    )
    (net (code "45") (name "/DIO3") (class "Default")
      (node (ref "R39") (pin "2") (pinfunction "2_2") (pintype "passive"))
    )
    (net (code "46") (name "/DIO3_1") (class "Default")
      (node (ref "R39") (pin "1") (pinfunction "1_1") (pintype "passive"))
    )
    (net (code "47") (name "/DIO4") (class "Default")
      (node (ref "R38") (pin "2") (pinfunction "2_2") (pintype "passive"))
    )
    (net (code "48") (name "/DIO4_1") (class "Default")
      (node (ref "R38") (pin "1") (pinfunction "1_1") (pintype "passive"))
    )
    (net (code "49") (name "/DIO5") (class "Default")
      (node (ref "R37") (pin "2") (pinfunction "2_2") (pintype "passive"))
    )
    (net (code "50") (name "/DIO5_1") (class "Default")
      (node (ref "R37") (pin "1") (pinfunction "1_1") (pintype "passive"))
    )
    (net (code "51") (name "/DIR_M1") (class "Default")
      (node (ref "J11") (pin "1") (pinfunction "1_1") (pintype "passive"))
      (node (ref "R57") (pin "1") (pinfunction "1_1") (pintype "passive"))
    )
    (net (code "52") (name "/DIR_M1_1") (class "Default")
      (node (ref "R57") (pin "2") (pinfunction "2_2") (pintype "passive"))
    )
    (net (code "53") (name "/DIR_M2") (class "Default")
      (node (ref "J12") (pin "1") (pinfunction "1_1") (pintype "passive"))
      (node (ref "R62") (pin "1") (pinfunction "1_1") (pintype "passive"))
    )
    (net (code "54") (name "/DIR_M2_1") (class "Default")
      (node (ref "R62") (pin "2") (pinfunction "2_2") (pintype "passive"))
    )
    (net (code "55") (name "/DIR_M3") (class "Default")
      (node (ref "J16") (pin "1") (pinfunction "1_1") (pintype "passive"))
      (node (ref "R70") (pin "1") (pinfunction "1_1") (pintype "passive"))
    )
    (net (code "56") (name "/DIR_M3_1") (class "Default")
      (node (ref "R70") (pin "2") (pinfunction "2_2") (pintype "passive"))
    )
    (net (code "57") (name "/DIR_M4") (class "Default")
      (node (ref "J33") (pin "1") (pinfunction "1_1") (pintype "passive"))
      (node (ref "R80") (pin "1") (pinfunction "1_1") (pintype "passive"))
    )
    (net (code "58") (name "/DIR_M4_1") (class "Default")
      (node (ref "R80") (pin "2") (pinfunction "2_2") (pintype "passive"))
    )
    (net (code "59") (name "/DRDY_TEMP1") (class "Default")
      (node (ref "R51") (pin "2") (pinfunction "2_2") (pintype "passive"))
    )
    (net (code "60") (name "/DRDY_TEMP1_1") (class "Default")
      (node (ref "R51") (pin "1") (pinfunction "1_1") (pintype "passive"))
    )
    (net (code "61") (name "/DRDY_TEMP2") (class "Default")
      (node (ref "R52") (pin "2") (pinfunction "2_2") (pintype "passive"))
    )
    (net (code "62") (name "/DRDY_TEMP2_1") (class "Default")
      (node (ref "R52") (pin "1") (pinfunction "1_1") (pintype "passive"))
    )
    (net (code "63") (name "/EN_M1") (class "Default")
      (node (ref "J17") (pin "1") (pinfunction "1_1") (pintype "passive"))
      (node (ref "R58") (pin "1") (pinfunction "1_1") (pintype "passive"))
    )
    (net (code "64") (name "/EN_M1_1") (class "Default")
      (node (ref "R58") (pin "2") (pinfunction "2_2") (pintype "passive"))
    )
    (net (code "65") (name "/EN_M2") (class "Default")
      (node (ref "J34") (pin "1") (pinfunction "1_1") (pintype "passive"))
      (node (ref "R63") (pin "1") (pinfunction "1_1") (pintype "passive"))
    )
    (net (code "66") (name "/EN_M2_1") (class "Default")
      (node (ref "R63") (pin "2") (pinfunction "2_2") (pintype "passive"))
    )
    (net (code "67") (name "/EN_M3") (class "Default")
      (node (ref "J14") (pin "1") (pinfunction "1_1") (pintype "passive"))
      (node (ref "R72") (pin "1") (pinfunction "1_1") (pintype "passive"))
    )
    (net (code "68") (name "/EN_M3_1") (class "Default")
      (node (ref "R72") (pin "2") (pinfunction "2_2") (pintype "passive"))
    )
    (net (code "69") (name "/EN_M4") (class "Default")
      (node (ref "J25") (pin "1") (pinfunction "1_1") (pintype "passive"))
      (node (ref "R81") (pin "1") (pinfunction "1_1") (pintype "passive"))
    )
    (net (code "70") (name "/EN_M4_1") (class "Default")
      (node (ref "R81") (pin "2") (pinfunction "2_2") (pintype "passive"))
    )
    (net (code "71") (name "/EXT_INT_GPS") (class "Default")
      (node (ref "J67") (pin "1") (pinfunction "1_1") (pintype "passive"))
      (node (ref "R22") (pin "1") (pinfunction "1_1") (pintype "passive"))
    )
    (net (code "72") (name "/EXT_INT_GPS_1") (class "Default")
      (node (ref "R22") (pin "2") (pinfunction "2_2") (pintype "passive"))
    )
    (net (code "73") (name "/FAULT_TEMP1") (class "Default")
      (node (ref "R50") (pin "2") (pinfunction "2_2") (pintype "passive"))
    )
    (net (code "74") (name "/FAULT_TEMP1_1") (class "Default")
      (node (ref "R50") (pin "1") (pinfunction "1_1") (pintype "passive"))
    )
    (net (code "75") (name "/FAULT_TEMP2") (class "Default")
      (node (ref "R49") (pin "2") (pinfunction "2_2") (pintype "passive"))
    )
    (net (code "76") (name "/FAULT_TEMP2_1") (class "Default")
      (node (ref "R49") (pin "1") (pinfunction "1_1") (pintype "passive"))
    )
    (net (code "77") (name "/FDC1_CONN") (class "Default")
      (node (ref "J1") (pin "02") (pinfunction "02_02") (pintype "passive"))
    )
    (net (code "78") (name "/FDC2_CONN") (class "Default")
      (node (ref "J1") (pin "04") (pinfunction "04_04") (pintype "passive"))
    )
    (net (code "79") (name "/FDC3_CONN") (class "Default")
      (node (ref "J1") (pin "06") (pinfunction "06_06") (pintype "passive"))
    )
    (net (code "80") (name "/FDC4_CONN") (class "Default")
      (node (ref "J1") (pin "08") (pinfunction "08_08") (pintype "passive"))
    )
    (net (code "81") (name "/FDC5_CONN") (class "Default")
      (node (ref "J1") (pin "10") (pinfunction "10_10") (pintype "passive"))
    )
    (net (code "82") (name "/FDC6_CONN") (class "Default")
      (node (ref "J1") (pin "12") (pinfunction "12_12") (pintype "passive"))
    )
    (net (code "83") (name "/FDC7_CONN") (class "Default")
      (node (ref "J1") (pin "14") (pinfunction "14_14") (pintype "passive"))
    )
    (net (code "84") (name "/FDC8_CONN") (class "Default")
      (node (ref "J1") (pin "16") (pinfunction "16_16") (pintype "passive"))
    )
    (net (code "85") (name "/IBAT_FB") (class "Default")
      (node (ref "J18") (pin "1") (pinfunction "1_1") (pintype "passive"))
      (node (ref "R71") (pin "2") (pinfunction "2_2") (pintype "passive"))
    )
    (net (code "86") (name "/IBAT_FB_1") (class "Default")
      (node (ref "R71") (pin "1") (pinfunction "1_1") (pintype "passive"))
    )
    (net (code "87") (name "/IBAT_MOTOR1_FB") (class "Default")
      (node (ref "J39") (pin "1") (pinfunction "1_1") (pintype "passive"))
      (node (ref "R74") (pin "2") (pinfunction "2_2") (pintype "passive"))
    )
    (net (code "88") (name "/IBAT_MOTOR1_FB_1") (class "Default")
      (node (ref "R74") (pin "1") (pinfunction "1_1") (pintype "passive"))
    )
    (net (code "89") (name "/IBAT_MOTOR2_FB") (class "Default")
      (node (ref "J27") (pin "1") (pinfunction "1_1") (pintype "passive"))
      (node (ref "R77") (pin "2") (pinfunction "2_2") (pintype "passive"))
    )
    (net (code "90") (name "/IBAT_MOTOR2_FB_1") (class "Default")
      (node (ref "R77") (pin "1") (pinfunction "1_1") (pintype "passive"))
    )
    (net (code "91") (name "/IMOTOR1") (class "Default")
      (node (ref "J57") (pin "1") (pinfunction "1_1") (pintype "passive"))
      (node (ref "R60") (pin "1") (pinfunction "1_1") (pintype "passive"))
    )
    (net (code "92") (name "/IMOTOR1_1") (class "Default")
      (node (ref "R60") (pin "2") (pinfunction "2_2") (pintype "passive"))
    )
    (net (code "93") (name "/IMOTOR2") (class "Default")
      (node (ref "J36") (pin "1") (pinfunction "1_1") (pintype "passive"))
      (node (ref "R65") (pin "1") (pinfunction "1_1") (pintype "passive"))
    )
    (net (code "94") (name "/IMOTOR2_1") (class "Default")
      (node (ref "R65") (pin "2") (pinfunction "2_2") (pintype "passive"))
    )
    (net (code "95") (name "/IMOTOR3") (class "Default")
      (node (ref "J47") (pin "1") (pinfunction "1_1") (pintype "passive"))
      (node (ref "R75") (pin "1") (pinfunction "1_1") (pintype "passive"))
    )
    (net (code "96") (name "/IMOTOR3_1") (class "Default")
      (node (ref "R75") (pin "2") (pinfunction "2_2") (pintype "passive"))
    )
    (net (code "97") (name "/IMOTOR4") (class "Default")
      (node (ref "J58") (pin "1") (pinfunction "1_1") (pintype "passive"))
      (node (ref "R82") (pin "1") (pinfunction "1_1") (pintype "passive"))
    )
    (net (code "98") (name "/IMOTOR4_1") (class "Default")
      (node (ref "R82") (pin "2") (pinfunction "2_2") (pintype "passive"))
    )
    (net (code "99") (name "/INT_IMU") (class "Default")
      (node (ref "R45") (pin "2") (pinfunction "2_2") (pintype "passive"))
    )
    (net (code "100") (name "/INT_IMU_1") (class "Default")
      (node (ref "R45") (pin "1") (pinfunction "1_1") (pintype "passive"))
    )
    (net (code "101") (name "/MISO") (class "Default")
      (node (ref "R6") (pin "2") (pinfunction "2_2") (pintype "passive"))
    )
    (net (code "102") (name "/MISO_MEM") (class "Default")
      (node (ref "J75") (pin "1") (pinfunction "1_1") (pintype "passive"))
      (node (ref "R6") (pin "1") (pinfunction "1_1") (pintype "passive"))
      (node (ref "R66") (pin "2") (pinfunction "2_2") (pintype "passive"))
    )
    (net (code "103") (name "/MISO_MEM_1") (class "Default")
      (node (ref "R66") (pin "1") (pinfunction "1_1") (pintype "passive"))
    )
    (net (code "104") (name "/MISO_RADIO") (class "Default")
      (node (ref "J42") (pin "1") (pinfunction "1_1") (pintype "passive"))
      (node (ref "R53") (pin "2") (pinfunction "2_2") (pintype "passive"))
    )
    (net (code "105") (name "/MISO_RADIO_1") (class "Default")
      (node (ref "R53") (pin "1") (pinfunction "1_1") (pintype "passive"))
    )
    (net (code "106") (name "/MOSI") (class "Default")
      (node (ref "R7") (pin "2") (pinfunction "2_2") (pintype "passive"))
    )
    (net (code "107") (name "/MOSI_MEM") (class "Default")
      (node (ref "J78") (pin "1") (pinfunction "1_1") (pintype "passive"))
      (node (ref "R67") (pin "2") (pinfunction "2_2") (pintype "passive"))
      (node (ref "R7") (pin "1") (pinfunction "1_1") (pintype "passive"))
    )
    (net (code "108") (name "/MOSI_MEM_1") (class "Default")
      (node (ref "R67") (pin "1") (pinfunction "1_1") (pintype "passive"))
    )
    (net (code "109") (name "/MOSI_RADIO") (class "Default")
      (node (ref "J50") (pin "1") (pinfunction "1_1") (pintype "passive"))
      (node (ref "R54") (pin "2") (pinfunction "2_2") (pintype "passive"))
    )
    (net (code "110") (name "/MOSI_RADIO_1") (class "Default")
      (node (ref "R54") (pin "1") (pinfunction "1_1") (pintype "passive"))
    )
    (net (code "111") (name "/MOT1H_CONN") (class "Default")
      (node (ref "J1") (pin "20") (pinfunction "20_20") (pintype "passive"))
    )
    (net (code "112") (name "/MOT1L_CONN") (class "Default")
      (node (ref "J1") (pin "22") (pinfunction "22_22") (pintype "passive"))
    )
    (net (code "113") (name "/MOT2H_CONN") (class "Default")
      (node (ref "J1") (pin "32") (pinfunction "32_32") (pintype "passive"))
    )
    (net (code "114") (name "/MOT2L_CONN") (class "Default")
      (node (ref "J1") (pin "34") (pinfunction "34_34") (pintype "passive"))
    )
    (net (code "115") (name "/MOT3H_CONN") (class "Default")
      (node (ref "J1") (pin "26") (pinfunction "26_26") (pintype "passive"))
    )
    (net (code "116") (name "/MOT3L_CONN") (class "Default")
      (node (ref "J1") (pin "28") (pinfunction "28_28") (pintype "passive"))
    )
    (net (code "117") (name "/MOT4H_CONN") (class "Default")
      (node (ref "J1") (pin "38") (pinfunction "38_38") (pintype "passive"))
    )
    (net (code "118") (name "/MOT4L_CONN") (class "Default")
      (node (ref "J1") (pin "40") (pinfunction "40_40") (pintype "passive"))
    )
    (net (code "119") (name "/NRST_RADIO") (class "Default")
      (node (ref "J48") (pin "1") (pinfunction "1_1") (pintype "passive"))
      (node (ref "R35") (pin "2") (pinfunction "2_2") (pintype "passive"))
    )
    (net (code "120") (name "/NRST_RADIO_1") (class "Default")
      (node (ref "R35") (pin "1") (pinfunction "1_1") (pintype "passive"))
    )
    (net (code "122") (name "/PWM_M1") (class "Default")
      (node (ref "J13") (pin "1") (pinfunction "1_1") (pintype "passive"))
      (node (ref "R56") (pin "1") (pinfunction "1_1") (pintype "passive"))
    )
    (net (code "123") (name "/PWM_M1_1") (class "Default")
      (node (ref "R56") (pin "2") (pinfunction "2_2") (pintype "passive"))
    )
    (net (code "124") (name "/PWM_M2") (class "Default")
      (node (ref "J24") (pin "1") (pinfunction "1_1") (pintype "passive"))
      (node (ref "R61") (pin "1") (pinfunction "1_1") (pintype "passive"))
    )
    (net (code "125") (name "/PWM_M2_1") (class "Default")
      (node (ref "R61") (pin "2") (pinfunction "2_2") (pintype "passive"))
    )
    (net (code "126") (name "/PWM_M3") (class "Default")
      (node (ref "J35") (pin "1") (pinfunction "1_1") (pintype "passive"))
      (node (ref "R69") (pin "1") (pinfunction "1_1") (pintype "passive"))
    )
    (net (code "127") (name "/PWM_M3_1") (class "Default")
      (node (ref "R69") (pin "2") (pinfunction "2_2") (pintype "passive"))
    )
    (net (code "128") (name "/PWM_M4") (class "Default")
      (node (ref "J46") (pin "1") (pinfunction "1_1") (pintype "passive"))
      (node (ref "R79") (pin "1") (pinfunction "1_1") (pintype "passive"))
    )
    (net (code "129") (name "/PWM_M4_1") (class "Default")
      (node (ref "R79") (pin "2") (pinfunction "2_2") (pintype "passive"))
    )
    (net (code "130") (name "/RF_MOD") (class "Default")
      (node (ref "J22") (pin "1") (pinfunction "1_1") (pintype "passive"))
      (node (ref "R36") (pin "2") (pinfunction "2_2") (pintype "passive"))
    )
    (net (code "131") (name "/RF_MOD_1") (class "Default")
      (node (ref "R36") (pin "1") (pinfunction "1_1") (pintype "passive"))
    )
    (net (code "132") (name "/RST_GPS") (class "Default")
      (node (ref "J69") (pin "1") (pinfunction "1_1") (pintype "passive"))
      (node (ref "R33") (pin "1") (pinfunction "1_1") (pintype "passive"))
    )
    (net (code "133") (name "/RST_GPS_1") (class "Default")
      (node (ref "R33") (pin "2") (pinfunction "2_2") (pintype "passive"))
    )
    (net (code "134") (name "/SCK_MEM") (class "Default")
      (node (ref "J76") (pin "1") (pinfunction "1_1") (pintype "passive"))
      (node (ref "R4") (pin "1") (pinfunction "1_1") (pintype "passive"))
      (node (ref "R64") (pin "2") (pinfunction "2_2") (pintype "passive"))
    )
    (net (code "135") (name "/SCK_MEM_1") (class "Default")
      (node (ref "R64") (pin "1") (pinfunction "1_1") (pintype "passive"))
    )
    (net (code "136") (name "/SCK_RADIO") (class "Default")
      (node (ref "J41") (pin "1") (pinfunction "1_1") (pintype "passive"))
      (node (ref "R55") (pin "2") (pinfunction "2_2") (pintype "passive"))
    )
    (net (code "137") (name "/SCK_RADIO_1") (class "Default")
      (node (ref "R55") (pin "1") (pinfunction "1_1") (pintype "passive"))
    )
    (net (code "138") (name "/SCL") (class "Default")
      (node (ref "J72") (pin "1") (pinfunction "1_1") (pintype "passive"))
      (node (ref "R26") (pin "1") (pinfunction "1_1") (pintype "passive"))
    )
    (net (code "139") (name "/SCLK") (class "Default")
      (node (ref "R4") (pin "2") (pinfunction "2_2") (pintype "passive"))
    )
    (net (code "140") (name "/SCL_1") (class "Default")
      (node (ref "R26") (pin "2") (pinfunction "2_2") (pintype "passive"))
    )
    (net (code "141") (name "/SDA") (class "Default")
      (node (ref "J70") (pin "1") (pinfunction "1_1") (pintype "passive"))
      (node (ref "R28") (pin "1") (pinfunction "1_1") (pintype "passive"))
    )
    (net (code "142") (name "/SDA_1") (class "Default")
      (node (ref "R28") (pin "2") (pinfunction "2_2") (pintype "passive"))
    )
    (net (code "143") (name "/SDCLK") (class "Default")
      (node (ref "J28") (pin "1") (pinfunction "1_1") (pintype "passive"))
    )
    (net (code "144") (name "/SDCMD") (class "Default")
      (node (ref "J29") (pin "1") (pinfunction "1_1") (pintype "passive"))
    )
    (net (code "145") (name "/SDDATA0") (class "Default")
      (node (ref "J7") (pin "1") (pinfunction "1_1") (pintype "passive"))
    )
    (net (code "146") (name "/SDDATA1") (class "Default")
      (node (ref "J8") (pin "1") (pinfunction "1_1") (pintype "passive"))
    )
    (net (code "147") (name "/SDDATA2") (class "Default")
      (node (ref "J20") (pin "1") (pinfunction "1_1") (pintype "passive"))
    )
    (net (code "148") (name "/SDDATA3") (class "Default")
      (node (ref "J21") (pin "1") (pinfunction "1_1") (pintype "passive"))
    )
    (net (code "149") (name "/TH1_CON_N") (class "Default")
      (node (ref "J84") (pin "13") (pinfunction "13_13") (pintype "passive"))
    )
    (net (code "150") (name "/TH1_CON_P") (class "Default")
      (node (ref "J84") (pin "11") (pinfunction "11_11") (pintype "passive"))
    )
    (net (code "151") (name "/TH2_CON_N") (class "Default")
      (node (ref "J84") (pin "19") (pinfunction "19_19") (pintype "passive"))
    )
    (net (code "152") (name "/TH2_CON_P") (class "Default")
      (node (ref "J84") (pin "17") (pinfunction "17_17") (pintype "passive"))
    )
    (net (code "153") (name "/UART_RX") (class "Default")
      (node (ref "J3") (pin "3") (pinfunction "3_3") (pintype "passive"))
      (node (ref "J45") (pin "1") (pinfunction "1_1") (pintype "passive"))
      (node (ref "R128") (pin "1") (pinfunction "1_1") (pintype "passive"))
    )
    (net (code "154") (name "/UART_RX_1") (class "Default")
      (node (ref "R128") (pin "2") (pinfunction "2_2") (pintype "passive"))
    )
    (net (code "155") (name "/UART_RX_GPS") (class "Default")
      (node (ref "J73") (pin "1") (pinfunction "1_1") (pintype "passive"))
      (node (ref "R19") (pin "1") (pinfunction "1_1") (pintype "passive"))
    )
    (net (code "156") (name "/UART_RX_GPS_1") (class "Default")
      (node (ref "R19") (pin "2") (pinfunction "2_2") (pintype "passive"))
    )
    (net (code "157") (name "/UART_TX") (class "Default")
      (node (ref "J3") (pin "2") (pinfunction "2_2") (pintype "passive"))
      (node (ref "J54") (pin "1") (pinfunction "1_1") (pintype "passive"))
      (node (ref "R129") (pin "1") (pinfunction "1_1") (pintype "passive"))
    )
    (net (code "158") (name "/UART_TX_1") (class "Default")
      (node (ref "R129") (pin "2") (pinfunction "2_2") (pintype "passive"))
    )
    (net (code "159") (name "/UART_TX_GPS") (class "Default")
      (node (ref "J71") (pin "1") (pinfunction "1_1") (pintype "passive"))
      (node (ref "R8") (pin "1") (pinfunction "1_1") (pintype "passive"))
    )
    (net (code "160") (name "/UART_TX_GPS_1") (class "Default")
      (node (ref "R8") (pin "2") (pinfunction "2_2") (pintype "passive"))
    )
    (net (code "161") (name "/VBAT_FB") (class "Default")
      (node (ref "J26") (pin "1") (pinfunction "1_1") (pintype "passive"))
      (node (ref "R73") (pin "2") (pinfunction "2_2") (pintype "passive"))
    )
    (net (code "162") (name "/VBAT_FB_1") (class "Default")
      (node (ref "R73") (pin "1") (pinfunction "1_1") (pintype "passive"))
    )
    (net (code "163") (name "/VBAT_MOTOR1_FB") (class "Default")
      (node (ref "J19") (pin "1") (pinfunction "1_1") (pintype "passive"))
      (node (ref "R76") (pin "2") (pinfunction "2_2") (pintype "passive"))
    )
    (net (code "164") (name "/VBAT_MOTOR1_FB_1") (class "Default")
      (node (ref "R76") (pin "1") (pinfunction "1_1") (pintype "passive"))
    )
    (net (code "165") (name "/VBAT_MOTOR2_FB") (class "Default")
      (node (ref "J40") (pin "1") (pinfunction "1_1") (pintype "passive"))
      (node (ref "R78") (pin "2") (pinfunction "2_2") (pintype "passive"))
    )
    (net (code "166") (name "/VBAT_MOTOR2_FB_1") (class "Default")
      (node (ref "R78") (pin "1") (pinfunction "1_1") (pintype "passive"))
    )
    (net (code "167") (name "GND") (class "Default")
      (node (ref "J1") (pin "01") (pinfunction "01_01") (pintype "passive"))
      (node (ref "J1") (pin "03") (pinfunction "03_03") (pintype "passive"))
      (node (ref "J1") (pin "05") (pinfunction "05_05") (pintype "passive"))
      (node (ref "J1") (pin "07") (pinfunction "07_07") (pintype "passive"))
      (node (ref "J1") (pin "09") (pinfunction "09_09") (pintype "passive"))
      (node (ref "J1") (pin "11") (pinfunction "11_11") (pintype "passive"))
      (node (ref "J1") (pin "13") (pinfunction "13_13") (pintype "passive"))
      (node (ref "J1") (pin "15") (pinfunction "15_15") (pintype "passive"))
      (node (ref "J1") (pin "17") (pinfunction "17_17") (pintype "passive"))
      (node (ref "J1") (pin "19") (pinfunction "19_19") (pintype "passive"))
      (node (ref "J1") (pin "21") (pinfunction "21_21") (pintype "passive"))
      (node (ref "J1") (pin "23") (pinfunction "23_23") (pintype "passive"))
      (node (ref "J1") (pin "25") (pinfunction "25_25") (pintype "passive"))
      (node (ref "J1") (pin "27") (pinfunction "27_27") (pintype "passive"))
      (node (ref "J1") (pin "29") (pinfunction "29_29") (pintype "passive"))
      (node (ref "J1") (pin "31") (pinfunction "31_31") (pintype "passive"))
      (node (ref "J1") (pin "33") (pinfunction "33_33") (pintype "passive"))
      (node (ref "J1") (pin "35") (pinfunction "35_35") (pintype "passive"))
      (node (ref "J1") (pin "37") (pinfunction "37_37") (pintype "passive"))
      (node (ref "J1") (pin "39") (pinfunction "39_39") (pintype "passive"))
      (node (ref "J15") (pin "1") (pinfunction "1_1") (pintype "passive"))
      (node (ref "J3") (pin "4") (pinfunction "4_4") (pintype "passive"))
      (node (ref "J32") (pin "1") (pinfunction "1_1") (pintype "passive"))
      (node (ref "J37") (pin "1") (pinfunction "1_1") (pintype "passive"))
      (node (ref "J38") (pin "1") (pinfunction "1_1") (pintype "passive"))
      (node (ref "J55") (pin "1") (pinfunction "1_1") (pintype "passive"))
      (node (ref "J56") (pin "1") (pinfunction "1_1") (pintype "passive"))
      (node (ref "J84") (pin "02") (pinfunction "02_02") (pintype "passive"))
      (node (ref "J84") (pin "04") (pinfunction "04_04") (pintype "passive"))
      (node (ref "J84") (pin "05") (pinfunction "05_05") (pintype "passive"))
      (node (ref "J84") (pin "06") (pinfunction "06_06") (pintype "passive"))
      (node (ref "J84") (pin "08") (pinfunction "08_08") (pintype "passive"))
      (node (ref "J84") (pin "09") (pinfunction "09_09") (pintype "passive"))
      (node (ref "J84") (pin "10") (pinfunction "10_10") (pintype "passive"))
      (node (ref "J84") (pin "12") (pinfunction "12_12") (pintype "passive"))
      (node (ref "J84") (pin "14") (pinfunction "14_14") (pintype "passive"))
      (node (ref "J84") (pin "15") (pinfunction "15_15") (pintype "passive"))
      (node (ref "J84") (pin "16") (pinfunction "16_16") (pintype "passive"))
      (node (ref "J84") (pin "18") (pinfunction "18_18") (pintype "passive"))
      (node (ref "J84") (pin "20") (pinfunction "20_20") (pintype "passive"))
      (node (ref "J84") (pin "21") (pinfunction "21_21") (pintype "passive"))
      (node (ref "J84") (pin "22") (pinfunction "22_22") (pintype "passive"))
      (node (ref "J84") (pin "23") (pinfunction "23_23") (pintype "passive"))
      (node (ref "J84") (pin "24") (pinfunction "24_24") (pintype "passive"))
      (node (ref "J84") (pin "25") (pinfunction "25_25") (pintype "passive"))
      (node (ref "J84") (pin "26") (pinfunction "26_26") (pintype "passive"))
      (node (ref "J84") (pin "27") (pinfunction "27_27") (pintype "passive"))
      (node (ref "J84") (pin "28") (pinfunction "28_28") (pintype "passive"))
      (node (ref "J84") (pin "29") (pinfunction "29_29") (pintype "passive"))
      (node (ref "J84") (pin "30") (pinfunction "30_30") (pintype "passive"))
      (node (ref "J84") (pin "31") (pinfunction "31_31") (pintype "passive"))
      (node (ref "J84") (pin "32") (pinfunction "32_32") (pintype "passive"))
      (node (ref "J84") (pin "34") (pinfunction "34_34") (pintype "passive"))
      (node (ref "J84") (pin "36") (pinfunction "36_36") (pintype "passive"))
      (node (ref "J84") (pin "38") (pinfunction "38_38") (pintype "passive"))
      (node (ref "J84") (pin "40") (pinfunction "40_40") (pintype "passive"))
    )
    (net (code "168") (name "unconnected-(J1-Pad18)") (class "Default")
      (node (ref "J1") (pin "18") (pinfunction "18_18") (pintype "passive+no_connect"))
    )
    (net (code "169") (name "unconnected-(J1-Pad24)") (class "Default")
      (node (ref "J1") (pin "24") (pinfunction "24_24") (pintype "passive+no_connect"))
    )
    (net (code "170") (name "unconnected-(J1-Pad30)") (class "Default")
      (node (ref "J1") (pin "30") (pinfunction "30_30") (pintype "passive+no_connect"))
    )
    (net (code "171") (name "unconnected-(J1-Pad36)") (class "Default")
      (node (ref "J1") (pin "36") (pinfunction "36_36") (pintype "passive+no_connect"))
    )
  )
)
